# lvc.net
KiCad netlist of a schematic drawn in EAGLE
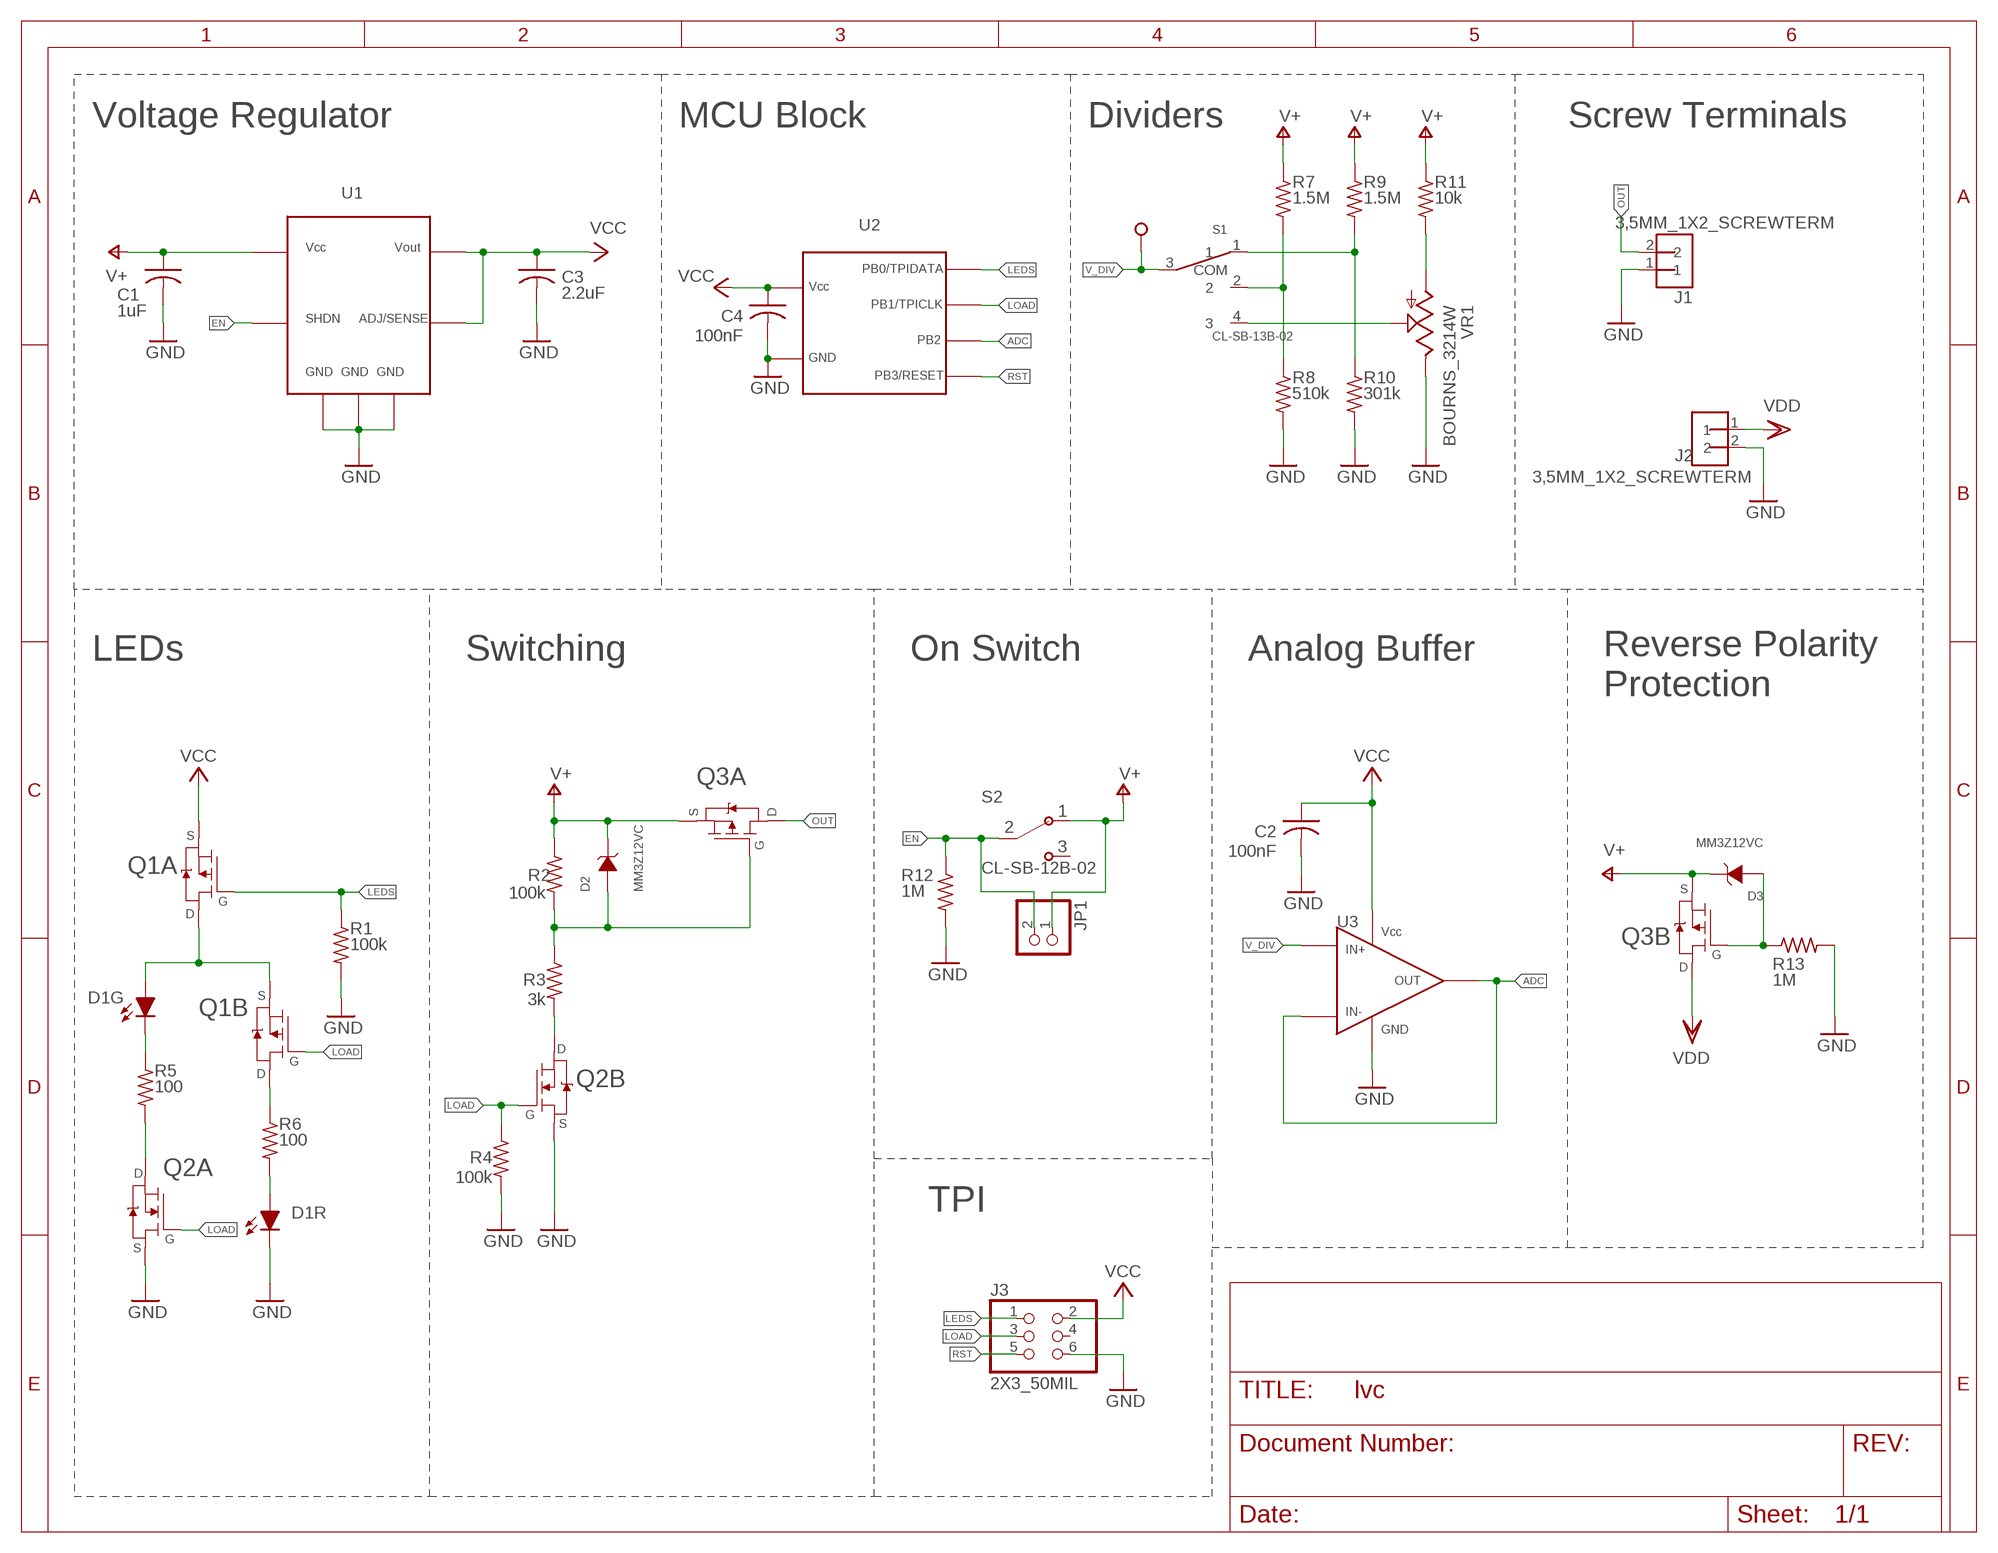
[diagram p0: schematic, sheet 1]

(export (version "E")
  (design (tool "Eeschema 10.0.6"))
  (components
    (comp (ref "C1")
      (value "1uF")
      (footprint "eagle-import:C0603")
      (libsource (lib "eagle-import") (part "C-USC0603"))
    )
    (comp (ref "C2")
      (value "100nF")
      (footprint "eagle-import:C0603")
      (libsource (lib "eagle-import") (part "C-USC0603"))
    )
    (comp (ref "C3")
      (value "2.2uF")
      (footprint "eagle-import:C0603")
      (libsource (lib "eagle-import") (part "C-USC0603"))
    )
    (comp (ref "C4")
      (value "100nF")
      (footprint "eagle-import:C0603")
      (libsource (lib "eagle-import") (part "C-USC0603"))
    )
    (comp (ref "D1")
      (value "LED-R/G_150141RV73100")
      (footprint "eagle-import:4-PLCC")
      (libsource (lib "eagle-import") (part "LED-R/G_150141RV73100"))
    )
    (comp (ref "D2")
      (value "MM3Z12VC")
      (footprint "eagle-import:SOD-323F")
      (libsource (lib "eagle-import") (part "MM3Z12VC"))
    )
    (comp (ref "D3")
      (value "MM3Z12VC")
      (footprint "eagle-import:SOD-323F")
      (libsource (lib "eagle-import") (part "MM3Z12VC"))
    )
    (comp (ref "J1")
      (value "3,5MM_1X2_SCREWTERM")
      (footprint "eagle-import:3.5MM_1X2")
      (libsource (lib "eagle-import") (part "3,5MM_1X2_SCREWTERM"))
    )
    (comp (ref "J2")
      (value "3,5MM_1X2_SCREWTERM")
      (footprint "eagle-import:3.5MM_1X2")
      (libsource (lib "eagle-import") (part "3,5MM_1X2_SCREWTERM"))
    )
    (comp (ref "J3")
      (value "2X3_50MIL")
      (footprint "eagle-import:50MIL_2X3")
      (libsource (lib "eagle-import") (part "2X3_50MIL"))
    )
    (comp (ref "JP1")
      (value "PINHD-1X2")
      (footprint "eagle-import:1X02")
      (libsource (lib "eagle-import") (part "PINHD-1X2"))
    )
    (comp (ref "Q1")
      (value "FDC6312P")
      (footprint "eagle-import:SOT23-6")
      (libsource (lib "eagle-import") (part "FDC6312P"))
    )
    (comp (ref "Q2")
      (value "PMGD280UN")
      (footprint "eagle-import:6-TSSOP")
      (libsource (lib "eagle-import") (part "PMGD280UN"))
    )
    (comp (ref "Q3")
      (value "SI7997DP")
      (footprint "eagle-import:POWERPAK-SO-8-DUAL")
      (libsource (lib "eagle-import") (part "SI7997DP"))
    )
    (comp (ref "R1")
      (value "100k")
      (footprint "eagle-import:R0603")
      (libsource (lib "eagle-import") (part "R-US_R0603"))
    )
    (comp (ref "R2")
      (value "100k")
      (footprint "eagle-import:R0603")
      (libsource (lib "eagle-import") (part "R-US_R0603"))
    )
    (comp (ref "R3")
      (value "3k")
      (footprint "eagle-import:R0603")
      (libsource (lib "eagle-import") (part "R-US_R0603"))
    )
    (comp (ref "R4")
      (value "100k")
      (footprint "eagle-import:R0603")
      (libsource (lib "eagle-import") (part "R-US_R0603"))
    )
    (comp (ref "R5")
      (value "100")
      (footprint "eagle-import:R0603")
      (libsource (lib "eagle-import") (part "R-US_R0603"))
    )
    (comp (ref "R6")
      (value "100")
      (footprint "eagle-import:R0603")
      (libsource (lib "eagle-import") (part "R-US_R0603"))
    )
    (comp (ref "R7")
      (value "1.5M")
      (footprint "eagle-import:R0603")
      (libsource (lib "eagle-import") (part "R-US_R0603"))
    )
    (comp (ref "R8")
      (value "510k")
      (footprint "eagle-import:R0603")
      (libsource (lib "eagle-import") (part "R-US_R0603"))
    )
    (comp (ref "R9")
      (value "1.5M")
      (footprint "eagle-import:R0603")
      (libsource (lib "eagle-import") (part "R-US_R0603"))
    )
    (comp (ref "R10")
      (value "301k")
      (footprint "eagle-import:R0603")
      (libsource (lib "eagle-import") (part "R-US_R0603"))
    )
    (comp (ref "R11")
      (value "10k")
      (footprint "eagle-import:R0603")
      (libsource (lib "eagle-import") (part "R-US_R0603"))
    )
    (comp (ref "R12")
      (value "1M")
      (footprint "eagle-import:R0603")
      (libsource (lib "eagle-import") (part "R-US_R0603"))
    )
    (comp (ref "R13")
      (value "1M")
      (footprint "eagle-import:R0603")
      (libsource (lib "eagle-import") (part "R-US_R0603"))
    )
    (comp (ref "S1")
      (value "CL-SB-13B-02")
      (footprint "eagle-import:CL-SB-13B")
      (libsource (lib "eagle-import") (part "CL-SB-13B-02"))
    )
    (comp (ref "S2")
      (value "CL-SB-12B-02")
      (footprint "eagle-import:CL-SB-12B")
      (libsource (lib "eagle-import") (part "CL-SB-12B-02"))
    )
    (comp (ref "TP1")
      (value "TESTPOINT")
      (footprint "eagle-import:TP_2.5MM")
      (libsource (lib "eagle-import") (part "TESTPOINT"))
    )
    (comp (ref "U1")
      (value "LT3007")
      (footprint "eagle-import:SOT23-8")
      (libsource (lib "eagle-import") (part "LT3007"))
    )
    (comp (ref "U2")
      (value "ATTINY5")
      (footprint "eagle-import:SOT23-6")
      (libsource (lib "eagle-import") (part "ATTINY5"))
    )
    (comp (ref "U3")
      (value "LT1494")
      (footprint "eagle-import:8-MSOP")
      (libsource (lib "eagle-import") (part "LT1494"))
    )
    (comp (ref "VR1")
      (value "BOURNS_3214W")
      (footprint "eagle-import:J-LEAD_TOP_ADJ")
      (libsource (lib "eagle-import") (part "BOURNS_3214W"))
    )
  )
  (nets
    (net (code "1") (name "ADC") (class "Default")
      (node (ref "U2") (pin "4") (pinfunction "PB2_4") (pintype "bidirectional"))
      (node (ref "U3") (pin "P$2") (pinfunction "IN-_P$2") (pintype "bidirectional"))
      (node (ref "U3") (pin "P$6") (pinfunction "OUT_P$6") (pintype "bidirectional"))
    )
    (net (code "2") (name "EN") (class "Default")
      (node (ref "JP1") (pin "2") (pinfunction "2_2") (pintype "passive"))
      (node (ref "R12") (pin "1") (pinfunction "1_1") (pintype "passive"))
      (node (ref "S2") (pin "1") (pinfunction "P$1_1") (pintype "bidirectional"))
      (node (ref "U1") (pin "1") (pinfunction "SHDN_1") (pintype "bidirectional"))
    )
    (net (code "3") (name "GND") (class "Default")
      (node (ref "C1") (pin "2") (pinfunction "2_2") (pintype "passive"))
      (node (ref "C2") (pin "2") (pinfunction "2_2") (pintype "passive"))
      (node (ref "C3") (pin "2") (pinfunction "2_2") (pintype "passive"))
      (node (ref "C4") (pin "2") (pinfunction "2_2") (pintype "passive"))
      (node (ref "D1") (pin "3") (pinfunction "C_3") (pintype "passive"))
      (node (ref "J1") (pin "1") (pinfunction "1_1") (pintype "bidirectional"))
      (node (ref "J2") (pin "2") (pinfunction "2_2") (pintype "bidirectional"))
      (node (ref "J3") (pin "6") (pinfunction "6_6") (pintype "passive"))
      (node (ref "Q2") (pin "P$1") (pinfunction "S_P$1") (pintype "bidirectional"))
      (node (ref "Q2") (pin "P$4") (pinfunction "S_P$4") (pintype "bidirectional"))
      (node (ref "R1") (pin "2") (pinfunction "2_2") (pintype "passive"))
      (node (ref "R10") (pin "2") (pinfunction "2_2") (pintype "passive"))
      (node (ref "R12") (pin "2") (pinfunction "2_2") (pintype "passive"))
      (node (ref "R13") (pin "2") (pinfunction "2_2") (pintype "passive"))
      (node (ref "R4") (pin "2") (pinfunction "2_2") (pintype "passive"))
      (node (ref "R8") (pin "2") (pinfunction "2_2") (pintype "passive"))
      (node (ref "U1") (pin "2") (pinfunction "GND1_2") (pintype "bidirectional"))
      (node (ref "U1") (pin "3") (pinfunction "GND2_3") (pintype "bidirectional"))
      (node (ref "U1") (pin "4") (pinfunction "GND3_4") (pintype "bidirectional"))
      (node (ref "U2") (pin "2") (pinfunction "GND_2") (pintype "bidirectional"))
      (node (ref "U3") (pin "P$4") (pinfunction "GND_P$4") (pintype "bidirectional"))
      (node (ref "VR1") (pin "3") (pinfunction "E_3") (pintype "passive"))
    )
    (net (code "4") (name "LEDS") (class "Default")
      (node (ref "J3") (pin "1") (pinfunction "1_1") (pintype "passive"))
      (node (ref "Q1") (pin "1") (pinfunction "G_1") (pintype "bidirectional"))
      (node (ref "R1") (pin "1") (pinfunction "1_1") (pintype "passive"))
      (node (ref "U2") (pin "1") (pinfunction "PB0/TPID_1") (pintype "bidirectional"))
    )
    (net (code "5") (name "LOAD") (class "Default")
      (node (ref "J3") (pin "3") (pinfunction "3_3") (pintype "passive"))
      (node (ref "Q1") (pin "3") (pinfunction "G_3") (pintype "bidirectional"))
      (node (ref "Q2") (pin "P$2") (pinfunction "G_P$2") (pintype "bidirectional"))
      (node (ref "Q2") (pin "P$5") (pinfunction "G_P$5") (pintype "bidirectional"))
      (node (ref "R4") (pin "1") (pinfunction "1_1") (pintype "passive"))
      (node (ref "U2") (pin "3") (pinfunction "PB1/TPICLK_3") (pintype "bidirectional"))
    )
    (net (code "6") (name "Net-(D1A-A)") (class "Default")
      (node (ref "D1") (pin "2") (pinfunction "A_2") (pintype "passive"))
      (node (ref "Q1") (pin "2") (pinfunction "S_2") (pintype "bidirectional"))
      (node (ref "Q1") (pin "6") (pinfunction "D_6") (pintype "bidirectional"))
    )
    (net (code "7") (name "Net-(D1A-C)") (class "Default")
      (node (ref "D1") (pin "4") (pinfunction "C_4") (pintype "passive"))
      (node (ref "R5") (pin "1") (pinfunction "1_1") (pintype "passive"))
    )
    (net (code "8") (name "Net-(D1B-A)") (class "Default")
      (node (ref "D1") (pin "1") (pinfunction "A_1") (pintype "passive"))
      (node (ref "R6") (pin "2") (pinfunction "2_2") (pintype "passive"))
    )
    (net (code "9") (name "Net-(D2-A)") (class "Default")
      (node (ref "D2") (pin "1") (pinfunction "A_1") (pintype "bidirectional"))
      (node (ref "Q3") (pin "4") (pinfunction "G_4") (pintype "bidirectional"))
      (node (ref "R2") (pin "2") (pinfunction "2_2") (pintype "passive"))
      (node (ref "R3") (pin "1") (pinfunction "1_1") (pintype "passive"))
    )
    (net (code "10") (name "Net-(D3-A)") (class "Default")
      (node (ref "D3") (pin "1") (pinfunction "A_1") (pintype "bidirectional"))
      (node (ref "Q3") (pin "2") (pinfunction "G_2") (pintype "bidirectional"))
      (node (ref "R13") (pin "1") (pinfunction "1_1") (pintype "passive"))
    )
    (net (code "11") (name "Net-(Q1B-D)") (class "Default")
      (node (ref "Q1") (pin "4") (pinfunction "D_4") (pintype "bidirectional"))
      (node (ref "R6") (pin "1") (pinfunction "1_1") (pintype "passive"))
    )
    (net (code "12") (name "Net-(Q2A-D)") (class "Default")
      (node (ref "Q2") (pin "P$6") (pinfunction "D_P$6") (pintype "bidirectional"))
      (node (ref "R5") (pin "2") (pinfunction "2_2") (pintype "passive"))
    )
    (net (code "13") (name "Net-(Q2B-D)") (class "Default")
      (node (ref "Q2") (pin "P$3") (pinfunction "D_P$3") (pintype "bidirectional"))
      (node (ref "R3") (pin "2") (pinfunction "2_2") (pintype "passive"))
    )
    (net (code "14") (name "Net-(R7-Pad2)") (class "Default")
      (node (ref "R7") (pin "2") (pinfunction "2_2") (pintype "passive"))
      (node (ref "R8") (pin "1") (pinfunction "1_1") (pintype "passive"))
      (node (ref "S1") (pin "2") (pinfunction "2_2") (pintype "bidirectional"))
    )
    (net (code "15") (name "Net-(R10-Pad1)") (class "Default")
      (node (ref "R10") (pin "1") (pinfunction "1_1") (pintype "passive"))
      (node (ref "R9") (pin "2") (pinfunction "2_2") (pintype "passive"))
      (node (ref "S1") (pin "1") (pinfunction "1_1") (pintype "bidirectional"))
    )
    (net (code "16") (name "Net-(S1-3)") (class "Default")
      (node (ref "S1") (pin "4") (pinfunction "3_4") (pintype "bidirectional"))
      (node (ref "VR1") (pin "2") (pinfunction "S_2") (pintype "passive"))
    )
    (net (code "17") (name "Net-(VR1-A)") (class "Default")
      (node (ref "R11") (pin "2") (pinfunction "2_2") (pintype "passive"))
      (node (ref "VR1") (pin "1") (pinfunction "A_1") (pintype "passive"))
    )
    (net (code "18") (name "OUT") (class "Default")
      (node (ref "J1") (pin "2") (pinfunction "2_2") (pintype "bidirectional"))
      (node (ref "Q3") (pin "5") (pinfunction "D_5") (pintype "bidirectional"))
      (node (ref "Q3") (pin "5L") (pinfunction "D_5L") (pintype "bidirectional"))
      (node (ref "Q3") (pin "6") (pinfunction "D_6") (pintype "bidirectional"))
    )
    (net (code "19") (name "RST") (class "Default")
      (node (ref "J3") (pin "5") (pinfunction "5_5") (pintype "passive"))
      (node (ref "U2") (pin "6") (pinfunction "PB3/RST_6") (pintype "bidirectional"))
    )
    (net (code "20") (name "V+") (class "Default")
      (node (ref "C1") (pin "1") (pinfunction "1_1") (pintype "passive"))
      (node (ref "D2") (pin "2") (pinfunction "C_2") (pintype "bidirectional"))
      (node (ref "D3") (pin "2") (pinfunction "C_2") (pintype "bidirectional"))
      (node (ref "JP1") (pin "1") (pinfunction "1_1") (pintype "passive"))
      (node (ref "Q3") (pin "1") (pinfunction "S_1") (pintype "bidirectional"))
      (node (ref "Q3") (pin "3") (pinfunction "S_3") (pintype "bidirectional"))
      (node (ref "R11") (pin "1") (pinfunction "1_1") (pintype "passive"))
      (node (ref "R2") (pin "1") (pinfunction "1_1") (pintype "passive"))
      (node (ref "R7") (pin "1") (pinfunction "1_1") (pintype "passive"))
      (node (ref "R9") (pin "1") (pinfunction "1_1") (pintype "passive"))
      (node (ref "S2") (pin "2") (pinfunction "P$2_2") (pintype "bidirectional"))
      (node (ref "U1") (pin "5") (pinfunction "VCC_5") (pintype "bidirectional"))
    )
    (net (code "21") (name "VCC") (class "Default")
      (node (ref "C2") (pin "1") (pinfunction "1_1") (pintype "passive"))
      (node (ref "C3") (pin "1") (pinfunction "1_1") (pintype "passive"))
      (node (ref "C4") (pin "1") (pinfunction "1_1") (pintype "passive"))
      (node (ref "J3") (pin "2") (pinfunction "2_2") (pintype "passive"))
      (node (ref "Q1") (pin "5") (pinfunction "S_5") (pintype "bidirectional"))
      (node (ref "U1") (pin "7") (pinfunction "OUT_7") (pintype "bidirectional"))
      (node (ref "U1") (pin "8") (pinfunction "ADJ/SENSE_8") (pintype "bidirectional"))
      (node (ref "U2") (pin "5") (pinfunction "VCC_5") (pintype "bidirectional"))
      (node (ref "U3") (pin "P$7") (pinfunction "VCC_P$7") (pintype "bidirectional"))
    )
    (net (code "22") (name "VDD") (class "Default")
      (node (ref "J2") (pin "1") (pinfunction "1_1") (pintype "bidirectional"))
      (node (ref "Q3") (pin "7") (pinfunction "D_7") (pintype "bidirectional"))
      (node (ref "Q3") (pin "8") (pinfunction "D_8") (pintype "bidirectional"))
      (node (ref "Q3") (pin "8L") (pinfunction "D_8L") (pintype "bidirectional"))
    )
    (net (code "23") (name "V_DIV") (class "Default")
      (node (ref "S1") (pin "3") (pinfunction "COM_3") (pintype "bidirectional"))
      (node (ref "TP1") (pin "P$1") (pinfunction "P$1_P$1") (pintype "bidirectional"))
      (node (ref "U3") (pin "P$3") (pinfunction "IN+_P$3") (pintype "bidirectional"))
    )
    (net (code "24") (name "unconnected-(J3-Pad4)") (class "Default")
      (node (ref "J3") (pin "4") (pinfunction "4_4") (pintype "passive"))
    )
    (net (code "25") (name "unconnected-(S2-P$3-Pad3)") (class "Default")
      (node (ref "S2") (pin "3") (pinfunction "P$3_3") (pintype "bidirectional"))
    )
  )
)
